# a52-flashcart-v2.net
KiCad netlist of a schematic drawn in EAGLE
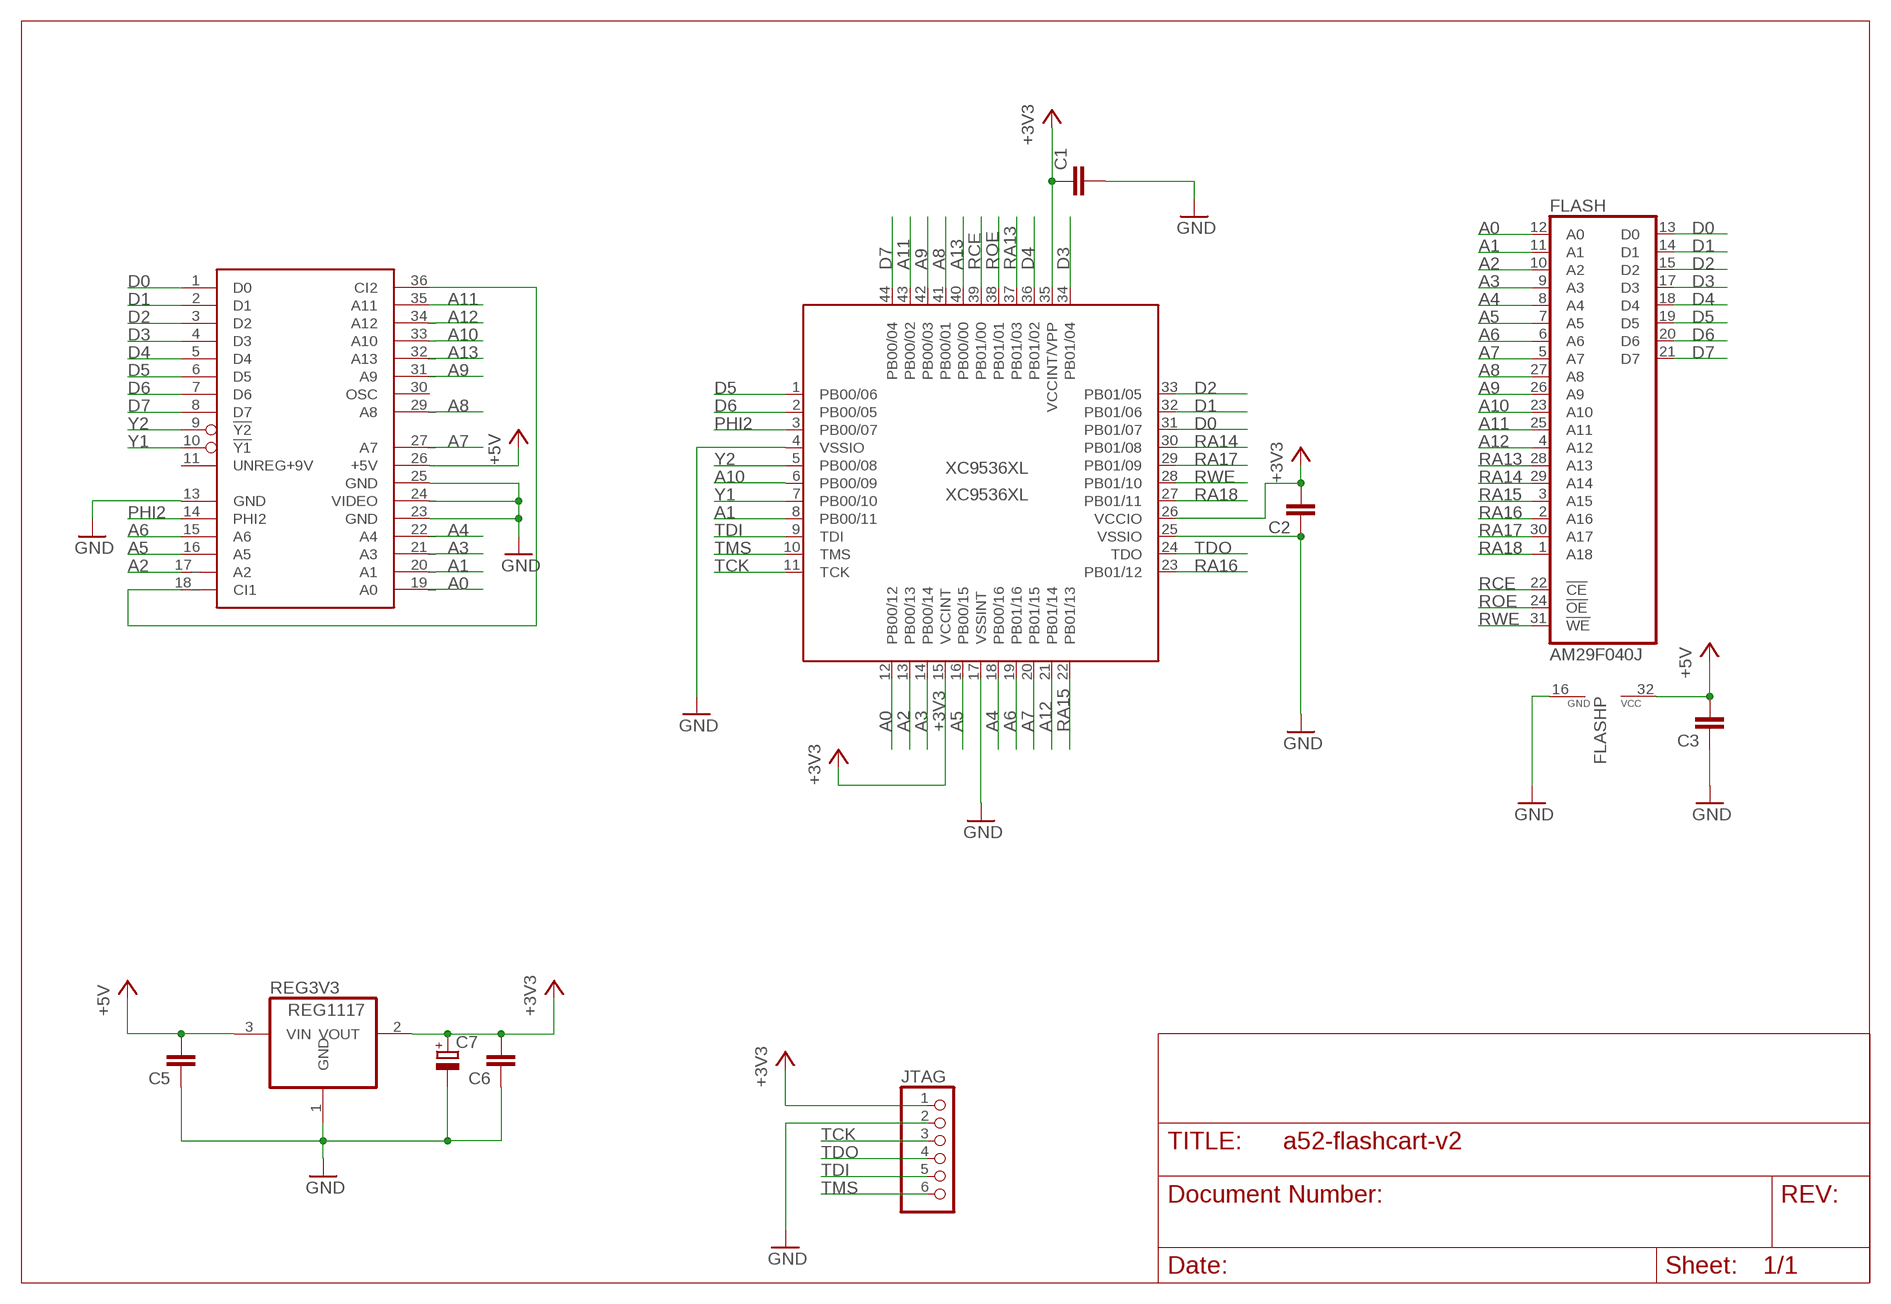
[diagram p0: schematic, sheet 1]

(export (version "E")
  (design (tool "Eeschema 10.0.6"))
  (components
    (comp (ref "C1")
      (value "C-EUC0603")
      (footprint "eagle-import:C0603")
      (libsource (lib "eagle-import") (part "C-EUC0603"))
    )
    (comp (ref "C2")
      (value "C-EUC0603")
      (footprint "eagle-import:C0603")
      (libsource (lib "eagle-import") (part "C-EUC0603"))
    )
    (comp (ref "C3")
      (value "C-EUC0603")
      (footprint "eagle-import:C0603")
      (libsource (lib "eagle-import") (part "C-EUC0603"))
    )
    (comp (ref "C5")
      (value "C-EUC0603")
      (footprint "eagle-import:C0603")
      (libsource (lib "eagle-import") (part "C-EUC0603"))
    )
    (comp (ref "C6")
      (value "C-EUC0603")
      (footprint "eagle-import:C0603")
      (libsource (lib "eagle-import") (part "C-EUC0603"))
    )
    (comp (ref "C7")
      (value "CPOL-EUSMCC")
      (footprint "eagle-import:SMC_C")
      (libsource (lib "eagle-import") (part "CPOL-EUSMCC"))
    )
    (comp (ref "FLASH")
      (value "AM29F040J")
      (footprint "eagle-import:PLCC32R")
      (libsource (lib "eagle-import") (part "AM29F040J"))
    )
    (comp (ref "JTAG")
      (value "PINHD-1X6")
      (footprint "eagle-import:1X06")
      (libsource (lib "eagle-import") (part "PINHD-1X6"))
    )
    (comp (ref "REG3V3")
      (value "REG1117")
      (footprint "eagle-import:SOT223")
      (libsource (lib "eagle-import") (part "REG1117"))
    )
    (comp (ref "U$1")
      (value "ATARI-5200-TS")
      (footprint "eagle-import:ATARI-5200-SMALL-T")
      (libsource (lib "eagle-import") (part "ATARI-5200-TS"))
    )
    (comp (ref "XC9536XL")
      (value "XC9536XL")
      (footprint "eagle-import:SQFP-S-10X10-44")
      (fields (field (name "MPN") "XC9536-15VQG44C"))
      (libsource (lib "eagle-import") (part "XC9536_44VQ"))
    )
  )
  (nets
    (net (code "1") (name "+3V3") (class "Default")
      (node (ref "C1") (pin "1") (pinfunction "1_1") (pintype "passive"))
      (node (ref "C2") (pin "2") (pinfunction "2_2") (pintype "passive"))
      (node (ref "C6") (pin "2") (pinfunction "2_2") (pintype "passive"))
      (node (ref "C7") (pin "+") (pinfunction "+_+") (pintype "passive"))
      (node (ref "JTAG") (pin "1") (pinfunction "1_1") (pintype "passive"))
      (node (ref "REG3V3") (pin "2") (pinfunction "VOUT_2") (pintype "output"))
      (node (ref "XC9536XL") (pin "15") (pinfunction "VCCINT_15") (pintype "power_in"))
      (node (ref "XC9536XL") (pin "26") (pinfunction "VCCIO_26") (pintype "power_in"))
      (node (ref "XC9536XL") (pin "35") (pinfunction "VCCINT/VPP_35") (pintype "input"))
    )
    (net (code "2") (name "+5V") (class "Default")
      (node (ref "C3") (pin "2") (pinfunction "2_2") (pintype "passive"))
      (node (ref "C5") (pin "2") (pinfunction "2_2") (pintype "passive"))
      (node (ref "FLASH") (pin "32") (pinfunction "VCC_32") (pintype "power_in"))
      (node (ref "REG3V3") (pin "3") (pinfunction "VIN_3") (pintype "input"))
      (node (ref "U$1") (pin "26_") (pinfunction "+5V_26_") (pintype "bidirectional"))
    )
    (net (code "3") (name "/A0") (class "Default")
      (node (ref "FLASH") (pin "12") (pinfunction "A0_12") (pintype "input"))
      (node (ref "U$1") (pin "19_") (pinfunction "A0_19_") (pintype "bidirectional"))
      (node (ref "XC9536XL") (pin "12") (pinfunction "PB00/12_12") (pintype "bidirectional"))
    )
    (net (code "4") (name "/A1") (class "Default")
      (node (ref "FLASH") (pin "11") (pinfunction "A1_11") (pintype "input"))
      (node (ref "U$1") (pin "20_") (pinfunction "A1_20_") (pintype "bidirectional"))
      (node (ref "XC9536XL") (pin "8") (pinfunction "PB00/11_8") (pintype "bidirectional"))
    )
    (net (code "5") (name "/A2") (class "Default")
      (node (ref "FLASH") (pin "10") (pinfunction "A2_10") (pintype "input"))
      (node (ref "U$1") (pin "17_") (pinfunction "A2_17_") (pintype "bidirectional"))
      (node (ref "XC9536XL") (pin "13") (pinfunction "PB00/13_13") (pintype "bidirectional"))
    )
    (net (code "6") (name "/A3") (class "Default")
      (node (ref "FLASH") (pin "9") (pinfunction "A3_9") (pintype "input"))
      (node (ref "U$1") (pin "21_") (pinfunction "A3_21_") (pintype "bidirectional"))
      (node (ref "XC9536XL") (pin "14") (pinfunction "PB00/14_14") (pintype "bidirectional"))
    )
    (net (code "7") (name "/A4") (class "Default")
      (node (ref "FLASH") (pin "8") (pinfunction "A4_8") (pintype "input"))
      (node (ref "U$1") (pin "22_") (pinfunction "A4_22_") (pintype "bidirectional"))
      (node (ref "XC9536XL") (pin "18") (pinfunction "PB00/16_18") (pintype "bidirectional"))
    )
    (net (code "8") (name "/A5") (class "Default")
      (node (ref "FLASH") (pin "7") (pinfunction "A5_7") (pintype "input"))
      (node (ref "U$1") (pin "16") (pinfunction "A5_16") (pintype "bidirectional"))
      (node (ref "XC9536XL") (pin "16") (pinfunction "PB00/15_16") (pintype "bidirectional"))
    )
    (net (code "9") (name "/A6") (class "Default")
      (node (ref "FLASH") (pin "6") (pinfunction "A6_6") (pintype "input"))
      (node (ref "U$1") (pin "15") (pinfunction "A6_15") (pintype "bidirectional"))
      (node (ref "XC9536XL") (pin "19") (pinfunction "PB01/16_19") (pintype "bidirectional"))
    )
    (net (code "10") (name "/A7") (class "Default")
      (node (ref "FLASH") (pin "5") (pinfunction "A7_5") (pintype "input"))
      (node (ref "U$1") (pin "27_") (pinfunction "A7_27_") (pintype "bidirectional"))
      (node (ref "XC9536XL") (pin "20") (pinfunction "PB01/15_20") (pintype "bidirectional"))
    )
    (net (code "11") (name "/A8") (class "Default")
      (node (ref "FLASH") (pin "27") (pinfunction "A8_27") (pintype "input"))
      (node (ref "U$1") (pin "29_") (pinfunction "A8_29_") (pintype "bidirectional"))
      (node (ref "XC9536XL") (pin "41") (pinfunction "PB00/01_41") (pintype "bidirectional"))
    )
    (net (code "12") (name "/A9") (class "Default")
      (node (ref "FLASH") (pin "26") (pinfunction "A9_26") (pintype "input"))
      (node (ref "U$1") (pin "31_") (pinfunction "A9_31_") (pintype "bidirectional"))
      (node (ref "XC9536XL") (pin "42") (pinfunction "PB00/03_42") (pintype "bidirectional"))
    )
    (net (code "13") (name "/A10") (class "Default")
      (node (ref "FLASH") (pin "23") (pinfunction "A10_23") (pintype "input"))
      (node (ref "U$1") (pin "33_") (pinfunction "A10_33_") (pintype "bidirectional"))
      (node (ref "XC9536XL") (pin "6") (pinfunction "PB00/09_6") (pintype "bidirectional"))
    )
    (net (code "14") (name "/A11") (class "Default")
      (node (ref "FLASH") (pin "25") (pinfunction "A11_25") (pintype "input"))
      (node (ref "U$1") (pin "35") (pinfunction "A11_35") (pintype "bidirectional"))
      (node (ref "XC9536XL") (pin "43") (pinfunction "PB00/02_43") (pintype "bidirectional"))
    )
    (net (code "15") (name "/A12") (class "Default")
      (node (ref "FLASH") (pin "4") (pinfunction "A12_4") (pintype "input"))
      (node (ref "U$1") (pin "34_") (pinfunction "A12_34_") (pintype "bidirectional"))
      (node (ref "XC9536XL") (pin "21") (pinfunction "PB01/14_21") (pintype "bidirectional"))
    )
    (net (code "16") (name "/A13") (class "Default")
      (node (ref "U$1") (pin "32_") (pinfunction "A13_32_") (pintype "bidirectional"))
      (node (ref "XC9536XL") (pin "40") (pinfunction "PB00/00_40") (pintype "bidirectional"))
    )
    (net (code "17") (name "/D0") (class "Default")
      (node (ref "FLASH") (pin "13") (pinfunction "D0_13") (pintype "tri_state"))
      (node (ref "U$1") (pin "1") (pinfunction "D0_1") (pintype "bidirectional"))
      (node (ref "XC9536XL") (pin "31") (pinfunction "PB01/07_31") (pintype "bidirectional"))
    )
    (net (code "18") (name "/D1") (class "Default")
      (node (ref "FLASH") (pin "14") (pinfunction "D1_14") (pintype "tri_state"))
      (node (ref "U$1") (pin "2") (pinfunction "D1_2") (pintype "bidirectional"))
      (node (ref "XC9536XL") (pin "32") (pinfunction "PB01/06_32") (pintype "bidirectional"))
    )
    (net (code "19") (name "/D2") (class "Default")
      (node (ref "FLASH") (pin "15") (pinfunction "D2_15") (pintype "tri_state"))
      (node (ref "U$1") (pin "3") (pinfunction "D2_3") (pintype "bidirectional"))
      (node (ref "XC9536XL") (pin "33") (pinfunction "PB01/05_33") (pintype "bidirectional"))
    )
    (net (code "20") (name "/D3") (class "Default")
      (node (ref "FLASH") (pin "17") (pinfunction "D3_17") (pintype "tri_state"))
      (node (ref "U$1") (pin "4") (pinfunction "D3_4") (pintype "bidirectional"))
      (node (ref "XC9536XL") (pin "34") (pinfunction "PB01/04_34") (pintype "bidirectional"))
    )
    (net (code "21") (name "/D4") (class "Default")
      (node (ref "FLASH") (pin "18") (pinfunction "D4_18") (pintype "tri_state"))
      (node (ref "U$1") (pin "5") (pinfunction "D4_5") (pintype "bidirectional"))
      (node (ref "XC9536XL") (pin "36") (pinfunction "PB01/02_36") (pintype "bidirectional"))
    )
    (net (code "22") (name "/D5") (class "Default")
      (node (ref "FLASH") (pin "19") (pinfunction "D5_19") (pintype "tri_state"))
      (node (ref "U$1") (pin "6") (pinfunction "D5_6") (pintype "bidirectional"))
      (node (ref "XC9536XL") (pin "1") (pinfunction "PB00/06_1") (pintype "bidirectional"))
    )
    (net (code "23") (name "/D6") (class "Default")
      (node (ref "FLASH") (pin "20") (pinfunction "D6_20") (pintype "tri_state"))
      (node (ref "U$1") (pin "7") (pinfunction "D6_7") (pintype "bidirectional"))
      (node (ref "XC9536XL") (pin "2") (pinfunction "PB00/05_2") (pintype "bidirectional"))
    )
    (net (code "24") (name "/D7") (class "Default")
      (node (ref "FLASH") (pin "21") (pinfunction "D7_21") (pintype "tri_state"))
      (node (ref "U$1") (pin "8") (pinfunction "D7_8") (pintype "bidirectional"))
      (node (ref "XC9536XL") (pin "44") (pinfunction "PB00/04_44") (pintype "bidirectional"))
    )
    (net (code "25") (name "/PHI2") (class "Default")
      (node (ref "U$1") (pin "14") (pinfunction "PHI2_14") (pintype "bidirectional"))
      (node (ref "XC9536XL") (pin "3") (pinfunction "PB00/07_3") (pintype "bidirectional"))
    )
    (net (code "26") (name "/RA13") (class "Default")
      (node (ref "FLASH") (pin "28") (pinfunction "A13_28") (pintype "input"))
      (node (ref "XC9536XL") (pin "37") (pinfunction "PB01/03_37") (pintype "bidirectional"))
    )
    (net (code "27") (name "/RA14") (class "Default")
      (node (ref "FLASH") (pin "29") (pinfunction "A14_29") (pintype "input"))
      (node (ref "XC9536XL") (pin "30") (pinfunction "PB01/08_30") (pintype "bidirectional"))
    )
    (net (code "28") (name "/RA15") (class "Default")
      (node (ref "FLASH") (pin "3") (pinfunction "A15_3") (pintype "input"))
      (node (ref "XC9536XL") (pin "22") (pinfunction "PB01/13_22") (pintype "bidirectional"))
    )
    (net (code "29") (name "/RA16") (class "Default")
      (node (ref "FLASH") (pin "2") (pinfunction "A16_2") (pintype "input"))
      (node (ref "XC9536XL") (pin "23") (pinfunction "PB01/12_23") (pintype "bidirectional"))
    )
    (net (code "30") (name "/RA17") (class "Default")
      (node (ref "FLASH") (pin "30") (pinfunction "A17_30") (pintype "input"))
      (node (ref "XC9536XL") (pin "29") (pinfunction "PB01/09_29") (pintype "bidirectional"))
    )
    (net (code "31") (name "/RA18") (class "Default")
      (node (ref "FLASH") (pin "1") (pinfunction "A18_1") (pintype "input"))
      (node (ref "XC9536XL") (pin "27") (pinfunction "PB01/11_27") (pintype "bidirectional"))
    )
    (net (code "32") (name "/RCE") (class "Default")
      (node (ref "FLASH") (pin "22") (pinfunction "~{CE}_22") (pintype "input"))
      (node (ref "XC9536XL") (pin "39") (pinfunction "PB01/00_39") (pintype "bidirectional"))
    )
    (net (code "33") (name "/ROE") (class "Default")
      (node (ref "FLASH") (pin "24") (pinfunction "~{OE}_24") (pintype "input"))
      (node (ref "XC9536XL") (pin "38") (pinfunction "PB01/01_38") (pintype "bidirectional"))
    )
    (net (code "34") (name "/RWE") (class "Default")
      (node (ref "FLASH") (pin "31") (pinfunction "~{WE}_31") (pintype "input"))
      (node (ref "XC9536XL") (pin "28") (pinfunction "PB01/10_28") (pintype "bidirectional"))
    )
    (net (code "35") (name "/TCK") (class "Default")
      (node (ref "JTAG") (pin "3") (pinfunction "3_3") (pintype "passive"))
      (node (ref "XC9536XL") (pin "11") (pinfunction "TCK_11") (pintype "input"))
    )
    (net (code "36") (name "/TDI") (class "Default")
      (node (ref "JTAG") (pin "5") (pinfunction "5_5") (pintype "passive"))
      (node (ref "XC9536XL") (pin "9") (pinfunction "TDI_9") (pintype "input"))
    )
    (net (code "37") (name "/TDO") (class "Default")
      (node (ref "JTAG") (pin "4") (pinfunction "4_4") (pintype "passive"))
      (node (ref "XC9536XL") (pin "24") (pinfunction "TDO_24") (pintype "output"))
    )
    (net (code "38") (name "/TMS") (class "Default")
      (node (ref "JTAG") (pin "6") (pinfunction "6_6") (pintype "passive"))
      (node (ref "XC9536XL") (pin "10") (pinfunction "TMS_10") (pintype "input"))
    )
    (net (code "39") (name "/Y1") (class "Default")
      (node (ref "U$1") (pin "10") (pinfunction "~{Y1}_10") (pintype "bidirectional"))
      (node (ref "XC9536XL") (pin "7") (pinfunction "PB00/10_7") (pintype "bidirectional"))
    )
    (net (code "40") (name "/Y2") (class "Default")
      (node (ref "U$1") (pin "9") (pinfunction "~{Y2}_9") (pintype "bidirectional"))
      (node (ref "XC9536XL") (pin "5") (pinfunction "PB00/08_5") (pintype "bidirectional"))
    )
    (net (code "41") (name "GND") (class "Default")
      (node (ref "C1") (pin "2") (pinfunction "2_2") (pintype "passive"))
      (node (ref "C2") (pin "1") (pinfunction "1_1") (pintype "passive"))
      (node (ref "C3") (pin "1") (pinfunction "1_1") (pintype "passive"))
      (node (ref "C5") (pin "1") (pinfunction "1_1") (pintype "passive"))
      (node (ref "C6") (pin "1") (pinfunction "1_1") (pintype "passive"))
      (node (ref "C7") (pin "-") (pinfunction "-_-") (pintype "passive"))
      (node (ref "FLASH") (pin "16") (pinfunction "GND_16") (pintype "power_in"))
      (node (ref "JTAG") (pin "2") (pinfunction "2_2") (pintype "passive"))
      (node (ref "REG3V3") (pin "1") (pinfunction "GND_1") (pintype "power_in"))
      (node (ref "U$1") (pin "13") (pinfunction "GND_13") (pintype "bidirectional"))
      (node (ref "U$1") (pin "23") (pinfunction "GND_23") (pintype "bidirectional"))
      (node (ref "U$1") (pin "24_") (pinfunction "VIDEO_24_") (pintype "bidirectional"))
      (node (ref "U$1") (pin "25") (pinfunction "GND_25") (pintype "bidirectional"))
      (node (ref "XC9536XL") (pin "17") (pinfunction "VSSINT_17") (pintype "power_in"))
      (node (ref "XC9536XL") (pin "25") (pinfunction "VSSIO_25") (pintype "power_in"))
      (node (ref "XC9536XL") (pin "4") (pinfunction "VSSIO_4") (pintype "power_in"))
    )
    (net (code "42") (name "Net-(U$1-CI1)") (class "Default")
      (node (ref "U$1") (pin "18_") (pinfunction "CI1_18_") (pintype "bidirectional"))
      (node (ref "U$1") (pin "36") (pinfunction "CI2_36") (pintype "bidirectional"))
    )
    (net (code "43") (name "unconnected-(U$1-OSC-Pad30)") (class "Default")
      (node (ref "U$1") (pin "30") (pinfunction "OSC_30") (pintype "bidirectional"))
    )
    (net (code "44") (name "unconnected-(U$1-UNREG+9V-Pad11)") (class "Default")
      (node (ref "U$1") (pin "11") (pinfunction "UNREG+9V_11") (pintype "bidirectional"))
    )
  )
)
